# comparator_mezzanine.net
KiCad netlist of a schematic drawn in Altium Designer
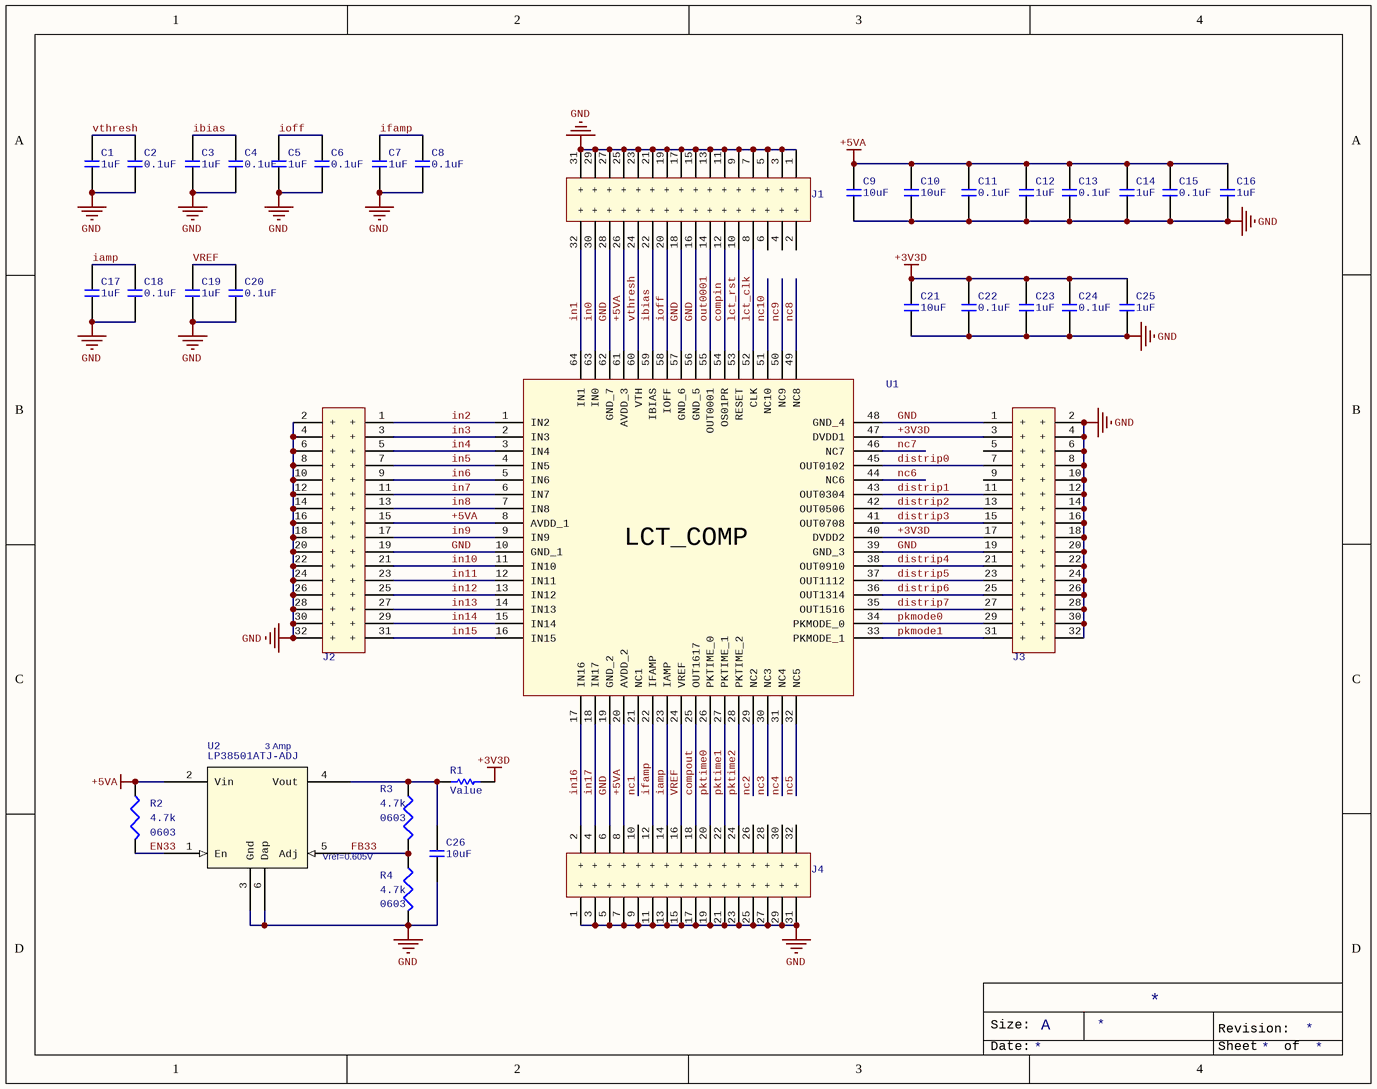
[diagram p0: comparator_mezzanine.SchDoc]

(export (version "E")
  (design (tool "Eeschema 10.0.6"))
  (components
    (comp (ref "C1")
      (value "1uF")
      (footprint "C0603")
      (description "CAP2, CER, 1.0uF, 10%, 25V, 0603")
      (libsource (lib "stdlib") (part "Murata/GRM188R61E105KA12D"))
    )
    (comp (ref "C2")
      (value "0.1uF")
      (footprint "C0603")
      (description "CAP-CER, 2, 0.1uF, 10%, 50V, 0603, X7R")
      (fields
        (field (name "MANUFACTURER") "AVX Corporation")
        (field (name "MANUFACTURER PART NUMBER") "06035C104KAT2A")
      )
      (libsource (lib "stdlib") (part "CAP/06035C104KAT2A"))
    )
    (comp (ref "C3")
      (value "1uF")
      (footprint "C0603")
      (description "CAP2, CER, 1.0uF, 10%, 25V, 0603")
      (libsource (lib "stdlib") (part "Murata/GRM188R61E105KA12D"))
    )
    (comp (ref "C4")
      (value "0.1uF")
      (footprint "C0603")
      (description "CAP-CER, 2, 0.1uF, 10%, 50V, 0603, X7R")
      (fields
        (field (name "MANUFACTURER") "AVX Corporation")
        (field (name "MANUFACTURER PART NUMBER") "06035C104KAT2A")
      )
      (libsource (lib "stdlib") (part "CAP/06035C104KAT2A"))
    )
    (comp (ref "C5")
      (value "1uF")
      (footprint "C0603")
      (description "CAP2, CER, 1.0uF, 10%, 25V, 0603")
      (libsource (lib "stdlib") (part "Murata/GRM188R61E105KA12D"))
    )
    (comp (ref "C6")
      (value "0.1uF")
      (footprint "C0603")
      (description "CAP-CER, 2, 0.1uF, 10%, 50V, 0603, X7R")
      (fields
        (field (name "MANUFACTURER") "AVX Corporation")
        (field (name "MANUFACTURER PART NUMBER") "06035C104KAT2A")
      )
      (libsource (lib "stdlib") (part "CAP/06035C104KAT2A"))
    )
    (comp (ref "C7")
      (value "1uF")
      (footprint "C0603")
      (description "CAP2, CER, 1.0uF, 10%, 25V, 0603")
      (libsource (lib "stdlib") (part "Murata/GRM188R61E105KA12D"))
    )
    (comp (ref "C8")
      (value "0.1uF")
      (footprint "C0603")
      (description "CAP-CER, 2, 0.1uF, 10%, 50V, 0603, X7R")
      (fields
        (field (name "MANUFACTURER") "AVX Corporation")
        (field (name "MANUFACTURER PART NUMBER") "06035C104KAT2A")
      )
      (libsource (lib "stdlib") (part "CAP/06035C104KAT2A"))
    )
    (comp (ref "C9")
      (value "10uF")
      (footprint "c1206")
      (description "CAP-CER, 2, 10uF, 10%, 35V, 1206")
      (fields
        (field (name "MANUFACTURER") "Taiyo Yuden")
        (field (name "MANUFACTURER PART NUMBER") "GMK316F106ZL-T")
      )
      (libsource (lib "stdlib") (part "CAP/GMK316F106ZL-T"))
    )
    (comp (ref "C10")
      (value "10uF")
      (footprint "c1206")
      (description "CAP-CER, 2, 10uF, 10%, 35V, 1206")
      (fields
        (field (name "MANUFACTURER") "Taiyo Yuden")
        (field (name "MANUFACTURER PART NUMBER") "GMK316F106ZL-T")
      )
      (libsource (lib "stdlib") (part "CAP/GMK316F106ZL-T"))
    )
    (comp (ref "C11")
      (value "0.1uF")
      (footprint "C0603")
      (description "CAP-CER, 2, 0.1uF, 10%, 50V, 0603, X7R")
      (fields
        (field (name "MANUFACTURER") "AVX Corporation")
        (field (name "MANUFACTURER PART NUMBER") "06035C104KAT2A")
      )
      (libsource (lib "stdlib") (part "CAP/06035C104KAT2A"))
    )
    (comp (ref "C12")
      (value "1uF")
      (footprint "C0603")
      (description "CAP2, CER, 1.0uF, 10%, 25V, 0603")
      (libsource (lib "stdlib") (part "Murata/GRM188R61E105KA12D"))
    )
    (comp (ref "C13")
      (value "0.1uF")
      (footprint "C0603")
      (description "CAP-CER, 2, 0.1uF, 10%, 50V, 0603, X7R")
      (fields
        (field (name "MANUFACTURER") "AVX Corporation")
        (field (name "MANUFACTURER PART NUMBER") "06035C104KAT2A")
      )
      (libsource (lib "stdlib") (part "CAP/06035C104KAT2A"))
    )
    (comp (ref "C14")
      (value "1uF")
      (footprint "C0603")
      (description "CAP2, CER, 1.0uF, 10%, 25V, 0603")
      (libsource (lib "stdlib") (part "Murata/GRM188R61E105KA12D"))
    )
    (comp (ref "C15")
      (value "0.1uF")
      (footprint "C0603")
      (description "CAP-CER, 2, 0.1uF, 10%, 50V, 0603, X7R")
      (fields
        (field (name "MANUFACTURER") "AVX Corporation")
        (field (name "MANUFACTURER PART NUMBER") "06035C104KAT2A")
      )
      (libsource (lib "stdlib") (part "CAP/06035C104KAT2A"))
    )
    (comp (ref "C16")
      (value "1uF")
      (footprint "C0603")
      (description "CAP2, CER, 1.0uF, 10%, 25V, 0603")
      (libsource (lib "stdlib") (part "Murata/GRM188R61E105KA12D"))
    )
    (comp (ref "C17")
      (value "1uF")
      (footprint "C0603")
      (description "CAP2, CER, 1.0uF, 10%, 25V, 0603")
      (libsource (lib "stdlib") (part "Murata/GRM188R61E105KA12D"))
    )
    (comp (ref "C18")
      (value "0.1uF")
      (footprint "C0603")
      (description "CAP-CER, 2, 0.1uF, 10%, 50V, 0603, X7R")
      (fields
        (field (name "MANUFACTURER") "AVX Corporation")
        (field (name "MANUFACTURER PART NUMBER") "06035C104KAT2A")
      )
      (libsource (lib "stdlib") (part "CAP/06035C104KAT2A"))
    )
    (comp (ref "C19")
      (value "1uF")
      (footprint "C0603")
      (description "CAP2, CER, 1.0uF, 10%, 25V, 0603")
      (libsource (lib "stdlib") (part "Murata/GRM188R61E105KA12D"))
    )
    (comp (ref "C20")
      (value "0.1uF")
      (footprint "C0603")
      (description "CAP-CER, 2, 0.1uF, 10%, 50V, 0603, X7R")
      (fields
        (field (name "MANUFACTURER") "AVX Corporation")
        (field (name "MANUFACTURER PART NUMBER") "06035C104KAT2A")
      )
      (libsource (lib "stdlib") (part "CAP/06035C104KAT2A"))
    )
    (comp (ref "C21")
      (value "10uF")
      (footprint "c1206")
      (description "CAP-CER, 2, 10uF, 10%, 35V, 1206")
      (fields
        (field (name "MANUFACTURER") "Taiyo Yuden")
        (field (name "MANUFACTURER PART NUMBER") "GMK316F106ZL-T")
      )
      (libsource (lib "stdlib") (part "CAP/GMK316F106ZL-T"))
    )
    (comp (ref "C22")
      (value "0.1uF")
      (footprint "C0603")
      (description "CAP-CER, 2, 0.1uF, 10%, 50V, 0603, X7R")
      (fields
        (field (name "MANUFACTURER") "AVX Corporation")
        (field (name "MANUFACTURER PART NUMBER") "06035C104KAT2A")
      )
      (libsource (lib "stdlib") (part "CAP/06035C104KAT2A"))
    )
    (comp (ref "C23")
      (value "1uF")
      (footprint "C0603")
      (description "CAP2, CER, 1.0uF, 10%, 25V, 0603")
      (libsource (lib "stdlib") (part "Murata/GRM188R61E105KA12D"))
    )
    (comp (ref "C24")
      (value "0.1uF")
      (footprint "C0603")
      (description "CAP-CER, 2, 0.1uF, 10%, 50V, 0603, X7R")
      (fields
        (field (name "MANUFACTURER") "AVX Corporation")
        (field (name "MANUFACTURER PART NUMBER") "06035C104KAT2A")
      )
      (libsource (lib "stdlib") (part "CAP/06035C104KAT2A"))
    )
    (comp (ref "C25")
      (value "1uF")
      (footprint "C0603")
      (description "CAP2, CER, 1.0uF, 10%, 25V, 0603")
      (libsource (lib "stdlib") (part "Murata/GRM188R61E105KA12D"))
    )
    (comp (ref "C26")
      (value "10uF")
      (footprint "c1206")
      (description "CAP-CER, 2, 10uF, 10%, 35V, 1206")
      (fields
        (field (name "MANUFACTURER") "Taiyo Yuden")
        (field (name "MANUFACTURER PART NUMBER") "GMK316F106ZL-T")
      )
      (libsource (lib "stdlib") (part "CAP/GMK316F106ZL-T"))
    )
    (comp (ref "J1")
      (value "HEADER 16x02")
      (footprint "HEADER 16X02")
      (libsource (lib "") (part "HEADER 16x02_1"))
    )
    (comp (ref "J2")
      (value "HEADER 16x02")
      (footprint "HEADER 16X02")
      (libsource (lib "") (part "HEADER 16x02_1"))
    )
    (comp (ref "J3")
      (value "HEADER 16x02")
      (footprint "HEADER 16X02")
      (libsource (lib "") (part "HEADER 16x02_2"))
    )
    (comp (ref "J4")
      (value "HEADER 16x02")
      (footprint "HEADER 16X02")
      (libsource (lib "stdlib") (part "HEADER 16x02"))
    )
    (comp (ref "R1")
      (value "Value")
      (footprint "R1206")
      (description "RES0, SMD 1206")
      (libsource (lib "stdlib") (part "RES SMD Generic 1206"))
    )
    (comp (ref "R2")
      (value "4.7k")
      (footprint "MC_S6/SM/R_0603_IPC")
      (description "RES SMD 4.7K OHM 1% 1/10W 0603")
      (fields
        (field (name "TOLERANCE") "±1%")
        (field (name "MANUFACTURER") "Panasonic Electronic Components")
        (field (name "SUPPLIER DEVICE PACKAGE") "0603")
      )
      (libsource (lib "ALCT_MEZ_SPARTAN6_Library") (part "ERJ-3EKF4701V"))
    )
    (comp (ref "R3")
      (value "4.7k")
      (footprint "MC_S6/SM/R_0603_IPC")
      (description "RES SMD 4.7K OHM 1% 1/10W 0603")
      (fields
        (field (name "TOLERANCE") "±1%")
        (field (name "MANUFACTURER") "Panasonic Electronic Components")
        (field (name "SUPPLIER DEVICE PACKAGE") "0603")
      )
      (libsource (lib "ALCT_MEZ_SPARTAN6_Library") (part "ERJ-3EKF4701V"))
    )
    (comp (ref "R4")
      (value "4.7k")
      (footprint "MC_S6/SM/R_0603_IPC")
      (description "RES SMD 4.7K OHM 1% 1/10W 0603")
      (fields
        (field (name "TOLERANCE") "±1%")
        (field (name "MANUFACTURER") "Panasonic Electronic Components")
        (field (name "SUPPLIER DEVICE PACKAGE") "0603")
      )
      (libsource (lib "ALCT_MEZ_SPARTAN6_Library") (part "ERJ-3EKF4701V"))
    )
    (comp (ref "U1")
      (value "UCLA/LCT_COMP")
      (footprint "TQFP-64 14x14mm")
      (description "UCLA LCT Comparator")
      (libsource (lib "stdlib") (part "UCLA/LCT_COMP"))
    )
    (comp (ref "U2")
      (value "LP38501ATJ-ADJ")
      (footprint "MC_S6/SM/TO263_THIN")
      (libsource (lib "ALCT_MEZ_SPARTAN6_Library") (part "LP38501ATJ-ADJ"))
    )
  )
  (nets
    (net (code "1") (name "+3V3D") (class "Default")
      (node (ref "C21") (pin "1") (pinfunction "5_1") (pintype "passive"))
      (node (ref "C22") (pin "2") (pinfunction "2_2") (pintype "passive"))
      (node (ref "C23") (pin "2") (pinfunction "2_2") (pintype "passive"))
      (node (ref "C24") (pin "2") (pinfunction "2_2") (pintype "passive"))
      (node (ref "C25") (pin "2") (pinfunction "2_2") (pintype "passive"))
      (node (ref "J3") (pin "17") (pinfunction "+_17") (pintype "passive"))
      (node (ref "J3") (pin "3") (pinfunction "+_3") (pintype "passive"))
      (node (ref "R1") (pin "2") (pinfunction "2_2") (pintype "passive"))
      (node (ref "U1") (pin "40") (pinfunction "DVDD2_40") (pintype "passive"))
      (node (ref "U1") (pin "47") (pinfunction "DVDD1_47") (pintype "passive"))
    )
    (net (code "2") (name "+5VA") (class "Default")
      (node (ref "C10") (pin "1") (pinfunction "5_1") (pintype "passive"))
      (node (ref "C11") (pin "2") (pinfunction "2_2") (pintype "passive"))
      (node (ref "C12") (pin "2") (pinfunction "2_2") (pintype "passive"))
      (node (ref "C13") (pin "2") (pinfunction "2_2") (pintype "passive"))
      (node (ref "C14") (pin "2") (pinfunction "2_2") (pintype "passive"))
      (node (ref "C15") (pin "2") (pinfunction "2_2") (pintype "passive"))
      (node (ref "C16") (pin "2") (pinfunction "2_2") (pintype "passive"))
      (node (ref "C9") (pin "1") (pinfunction "5_1") (pintype "passive"))
      (node (ref "J1") (pin "26") (pinfunction "+_26") (pintype "passive"))
      (node (ref "J2") (pin "15") (pinfunction "+_15") (pintype "passive"))
      (node (ref "J4") (pin "8") (pinfunction "+_8") (pintype "passive"))
      (node (ref "R2") (pin "1") (pinfunction "1_1") (pintype "passive"))
      (node (ref "U1") (pin "20") (pinfunction "AVDD_2_20") (pintype "passive"))
      (node (ref "U1") (pin "61") (pinfunction "AVDD_3_61") (pintype "passive"))
      (node (ref "U1") (pin "8") (pinfunction "AVDD_1_8") (pintype "passive"))
      (node (ref "U2") (pin "2") (pinfunction "Vin_2") (pintype "power_in"))
    )
    (net (code "3") (name "/EN33") (class "Default")
      (node (ref "R2") (pin "2") (pinfunction "2_2") (pintype "passive"))
      (node (ref "U2") (pin "1") (pinfunction "En_1") (pintype "input"))
    )
    (net (code "4") (name "/FB33") (class "Default")
      (node (ref "R3") (pin "2") (pinfunction "2_2") (pintype "passive"))
      (node (ref "R4") (pin "1") (pinfunction "1_1") (pintype "passive"))
      (node (ref "U2") (pin "5") (pinfunction "Adj_5") (pintype "input"))
    )
    (net (code "5") (name "/VREF") (class "Default")
      (node (ref "C19") (pin "2") (pinfunction "2_2") (pintype "passive"))
      (node (ref "C20") (pin "2") (pinfunction "2_2") (pintype "passive"))
      (node (ref "J4") (pin "16") (pinfunction "+_16") (pintype "passive"))
      (node (ref "U1") (pin "24") (pinfunction "VREF_24") (pintype "passive"))
    )
    (net (code "6") (name "/compin") (class "Default")
      (node (ref "J1") (pin "12") (pinfunction "+_12") (pintype "passive"))
      (node (ref "U1") (pin "54") (pinfunction "OS01PR_54") (pintype "passive"))
    )
    (net (code "7") (name "/compout") (class "Default")
      (node (ref "J4") (pin "18") (pinfunction "+_18") (pintype "passive"))
      (node (ref "U1") (pin "25") (pinfunction "OUT1617_25") (pintype "passive"))
    )
    (net (code "8") (name "/distrip0") (class "Default")
      (node (ref "J3") (pin "7") (pinfunction "+_7") (pintype "passive"))
      (node (ref "U1") (pin "45") (pinfunction "OUT0102_45") (pintype "passive"))
    )
    (net (code "9") (name "/distrip1") (class "Default")
      (node (ref "J3") (pin "11") (pinfunction "+_11") (pintype "passive"))
      (node (ref "U1") (pin "43") (pinfunction "OUT0304_43") (pintype "passive"))
    )
    (net (code "10") (name "/distrip2") (class "Default")
      (node (ref "J3") (pin "13") (pinfunction "+_13") (pintype "passive"))
      (node (ref "U1") (pin "42") (pinfunction "OUT0506_42") (pintype "passive"))
    )
    (net (code "11") (name "/distrip3") (class "Default")
      (node (ref "J3") (pin "15") (pinfunction "+_15") (pintype "passive"))
      (node (ref "U1") (pin "41") (pinfunction "OUT0708_41") (pintype "passive"))
    )
    (net (code "12") (name "/distrip4") (class "Default")
      (node (ref "J3") (pin "21") (pinfunction "+_21") (pintype "passive"))
      (node (ref "U1") (pin "38") (pinfunction "OUT0910_38") (pintype "passive"))
    )
    (net (code "13") (name "/distrip5") (class "Default")
      (node (ref "J3") (pin "23") (pinfunction "+_23") (pintype "passive"))
      (node (ref "U1") (pin "37") (pinfunction "OUT1112_37") (pintype "passive"))
    )
    (net (code "14") (name "/distrip6") (class "Default")
      (node (ref "J3") (pin "25") (pinfunction "+_25") (pintype "passive"))
      (node (ref "U1") (pin "36") (pinfunction "OUT1314_36") (pintype "passive"))
    )
    (net (code "15") (name "/distrip7") (class "Default")
      (node (ref "J3") (pin "27") (pinfunction "+_27") (pintype "passive"))
      (node (ref "U1") (pin "35") (pinfunction "OUT1516_35") (pintype "passive"))
    )
    (net (code "16") (name "/iamp") (class "Default")
      (node (ref "C17") (pin "2") (pinfunction "2_2") (pintype "passive"))
      (node (ref "C18") (pin "2") (pinfunction "2_2") (pintype "passive"))
      (node (ref "J4") (pin "14") (pinfunction "+_14") (pintype "passive"))
      (node (ref "U1") (pin "23") (pinfunction "IAMP_23") (pintype "passive"))
    )
    (net (code "17") (name "/ibias") (class "Default")
      (node (ref "C3") (pin "2") (pinfunction "2_2") (pintype "passive"))
      (node (ref "C4") (pin "2") (pinfunction "2_2") (pintype "passive"))
      (node (ref "J1") (pin "22") (pinfunction "+_22") (pintype "passive"))
      (node (ref "U1") (pin "59") (pinfunction "IBIAS_59") (pintype "passive"))
    )
    (net (code "18") (name "/ifamp") (class "Default")
      (node (ref "C7") (pin "2") (pinfunction "2_2") (pintype "passive"))
      (node (ref "C8") (pin "2") (pinfunction "2_2") (pintype "passive"))
      (node (ref "J4") (pin "12") (pinfunction "+_12") (pintype "passive"))
      (node (ref "U1") (pin "22") (pinfunction "IFAMP_22") (pintype "passive"))
    )
    (net (code "19") (name "/in0") (class "Default")
      (node (ref "J1") (pin "30") (pinfunction "+_30") (pintype "passive"))
      (node (ref "U1") (pin "63") (pinfunction "IN0_63") (pintype "passive"))
    )
    (net (code "20") (name "/in1") (class "Default")
      (node (ref "J1") (pin "32") (pinfunction "+_32") (pintype "passive"))
      (node (ref "U1") (pin "64") (pinfunction "IN1_64") (pintype "passive"))
    )
    (net (code "21") (name "/in2") (class "Default")
      (node (ref "J2") (pin "1") (pinfunction "+_1") (pintype "passive"))
      (node (ref "U1") (pin "1") (pinfunction "IN2_1") (pintype "passive"))
    )
    (net (code "22") (name "/in3") (class "Default")
      (node (ref "J2") (pin "3") (pinfunction "+_3") (pintype "passive"))
      (node (ref "U1") (pin "2") (pinfunction "IN3_2") (pintype "passive"))
    )
    (net (code "23") (name "/in4") (class "Default")
      (node (ref "J2") (pin "5") (pinfunction "+_5") (pintype "passive"))
      (node (ref "U1") (pin "3") (pinfunction "IN4_3") (pintype "passive"))
    )
    (net (code "24") (name "/in5") (class "Default")
      (node (ref "J2") (pin "7") (pinfunction "+_7") (pintype "passive"))
      (node (ref "U1") (pin "4") (pinfunction "IN5_4") (pintype "passive"))
    )
    (net (code "25") (name "/in6") (class "Default")
      (node (ref "J2") (pin "9") (pinfunction "+_9") (pintype "passive"))
      (node (ref "U1") (pin "5") (pinfunction "IN6_5") (pintype "passive"))
    )
    (net (code "26") (name "/in7") (class "Default")
      (node (ref "J2") (pin "11") (pinfunction "+_11") (pintype "passive"))
      (node (ref "U1") (pin "6") (pinfunction "IN7_6") (pintype "passive"))
    )
    (net (code "27") (name "/in8") (class "Default")
      (node (ref "J2") (pin "13") (pinfunction "+_13") (pintype "passive"))
      (node (ref "U1") (pin "7") (pinfunction "IN8_7") (pintype "passive"))
    )
    (net (code "28") (name "/in9") (class "Default")
      (node (ref "J2") (pin "17") (pinfunction "+_17") (pintype "passive"))
      (node (ref "U1") (pin "9") (pinfunction "IN9_9") (pintype "passive"))
    )
    (net (code "29") (name "/in10") (class "Default")
      (node (ref "J2") (pin "21") (pinfunction "+_21") (pintype "passive"))
      (node (ref "U1") (pin "11") (pinfunction "IN10_11") (pintype "passive"))
    )
    (net (code "30") (name "/in11") (class "Default")
      (node (ref "J2") (pin "23") (pinfunction "+_23") (pintype "passive"))
      (node (ref "U1") (pin "12") (pinfunction "IN11_12") (pintype "passive"))
    )
    (net (code "31") (name "/in12") (class "Default")
      (node (ref "J2") (pin "25") (pinfunction "+_25") (pintype "passive"))
      (node (ref "U1") (pin "13") (pinfunction "IN12_13") (pintype "passive"))
    )
    (net (code "32") (name "/in13") (class "Default")
      (node (ref "J2") (pin "27") (pinfunction "+_27") (pintype "passive"))
      (node (ref "U1") (pin "14") (pinfunction "IN13_14") (pintype "passive"))
    )
    (net (code "33") (name "/in14") (class "Default")
      (node (ref "J2") (pin "29") (pinfunction "+_29") (pintype "passive"))
      (node (ref "U1") (pin "15") (pinfunction "IN14_15") (pintype "passive"))
    )
    (net (code "34") (name "/in15") (class "Default")
      (node (ref "J2") (pin "31") (pinfunction "+_31") (pintype "passive"))
      (node (ref "U1") (pin "16") (pinfunction "IN15_16") (pintype "passive"))
    )
    (net (code "35") (name "/in16") (class "Default")
      (node (ref "J4") (pin "2") (pinfunction "+_2") (pintype "passive"))
      (node (ref "U1") (pin "17") (pinfunction "IN16_17") (pintype "passive"))
    )
    (net (code "36") (name "/in17") (class "Default")
      (node (ref "J4") (pin "4") (pinfunction "+_4") (pintype "passive"))
      (node (ref "U1") (pin "18") (pinfunction "IN17_18") (pintype "passive"))
    )
    (net (code "37") (name "/ioff") (class "Default")
      (node (ref "C5") (pin "2") (pinfunction "2_2") (pintype "passive"))
      (node (ref "C6") (pin "2") (pinfunction "2_2") (pintype "passive"))
      (node (ref "J1") (pin "20") (pinfunction "+_20") (pintype "passive"))
      (node (ref "U1") (pin "58") (pinfunction "IOFF_58") (pintype "passive"))
    )
    (net (code "38") (name "/lct_clk") (class "Default")
      (node (ref "J1") (pin "8") (pinfunction "+_8") (pintype "passive"))
      (node (ref "U1") (pin "52") (pinfunction "CLK_52") (pintype "passive"))
    )
    (net (code "39") (name "/lct_rst") (class "Default")
      (node (ref "J1") (pin "10") (pinfunction "+_10") (pintype "passive"))
      (node (ref "U1") (pin "53") (pinfunction "RESET_53") (pintype "passive"))
    )
    (net (code "40") (name "/nc1") (class "Default")
      (node (ref "U1") (pin "21") (pinfunction "NC1_21") (pintype "passive"))
    )
    (net (code "41") (name "/nc2") (class "Default")
      (node (ref "U1") (pin "29") (pinfunction "NC2_29") (pintype "passive"))
    )
    (net (code "42") (name "/nc3") (class "Default")
      (node (ref "U1") (pin "30") (pinfunction "NC3_30") (pintype "passive"))
    )
    (net (code "43") (name "/nc4") (class "Default")
      (node (ref "U1") (pin "31") (pinfunction "NC4_31") (pintype "passive"))
    )
    (net (code "44") (name "/nc5") (class "Default")
      (node (ref "U1") (pin "32") (pinfunction "NC5_32") (pintype "passive"))
    )
    (net (code "45") (name "/nc6") (class "Default")
      (node (ref "U1") (pin "44") (pinfunction "NC6_44") (pintype "passive"))
    )
    (net (code "46") (name "/nc7") (class "Default")
      (node (ref "U1") (pin "46") (pinfunction "NC7_46") (pintype "passive"))
    )
    (net (code "47") (name "/nc8") (class "Default")
      (node (ref "U1") (pin "49") (pinfunction "NC8_49") (pintype "passive"))
    )
    (net (code "48") (name "/nc9") (class "Default")
      (node (ref "U1") (pin "50") (pinfunction "NC9_50") (pintype "passive"))
    )
    (net (code "49") (name "/nc10") (class "Default")
      (node (ref "U1") (pin "51") (pinfunction "NC10_51") (pintype "passive"))
    )
    (net (code "50") (name "/out0001") (class "Default")
      (node (ref "J1") (pin "14") (pinfunction "+_14") (pintype "passive"))
      (node (ref "U1") (pin "55") (pinfunction "OUT0001_55") (pintype "passive"))
    )
    (net (code "51") (name "/pkmode0") (class "Default")
      (node (ref "J3") (pin "29") (pinfunction "+_29") (pintype "passive"))
      (node (ref "U1") (pin "34") (pinfunction "PKMODE_0_34") (pintype "passive"))
    )
    (net (code "52") (name "/pkmode1") (class "Default")
      (node (ref "J3") (pin "31") (pinfunction "+_31") (pintype "passive"))
      (node (ref "U1") (pin "33") (pinfunction "PKMODE_1_33") (pintype "passive"))
    )
    (net (code "53") (name "/pktime0") (class "Default")
      (node (ref "J4") (pin "20") (pinfunction "+_20") (pintype "passive"))
      (node (ref "U1") (pin "26") (pinfunction "PKTIME_0_26") (pintype "passive"))
    )
    (net (code "54") (name "/pktime1") (class "Default")
      (node (ref "J4") (pin "22") (pinfunction "+_22") (pintype "passive"))
      (node (ref "U1") (pin "27") (pinfunction "PKTIME_1_27") (pintype "passive"))
    )
    (net (code "55") (name "/pktime2") (class "Default")
      (node (ref "J4") (pin "24") (pinfunction "+_24") (pintype "passive"))
      (node (ref "U1") (pin "28") (pinfunction "PKTIME_2_28") (pintype "passive"))
    )
    (net (code "56") (name "/vthresh") (class "Default")
      (node (ref "C1") (pin "2") (pinfunction "2_2") (pintype "passive"))
      (node (ref "C2") (pin "2") (pinfunction "2_2") (pintype "passive"))
      (node (ref "J1") (pin "24") (pinfunction "+_24") (pintype "passive"))
      (node (ref "U1") (pin "60") (pinfunction "VTH_60") (pintype "passive"))
    )
    (net (code "57") (name "GND") (class "Default")
      (node (ref "C1") (pin "1") (pinfunction "5_1") (pintype "passive"))
      (node (ref "C10") (pin "2") (pinfunction "2_2") (pintype "passive"))
      (node (ref "C11") (pin "1") (pinfunction "5_1") (pintype "passive"))
      (node (ref "C12") (pin "1") (pinfunction "5_1") (pintype "passive"))
      (node (ref "C13") (pin "1") (pinfunction "5_1") (pintype "passive"))
      (node (ref "C14") (pin "1") (pinfunction "5_1") (pintype "passive"))
      (node (ref "C15") (pin "1") (pinfunction "5_1") (pintype "passive"))
      (node (ref "C16") (pin "1") (pinfunction "5_1") (pintype "passive"))
      (node (ref "C17") (pin "1") (pinfunction "5_1") (pintype "passive"))
      (node (ref "C18") (pin "1") (pinfunction "5_1") (pintype "passive"))
      (node (ref "C19") (pin "1") (pinfunction "5_1") (pintype "passive"))
      (node (ref "C2") (pin "1") (pinfunction "5_1") (pintype "passive"))
      (node (ref "C20") (pin "1") (pinfunction "5_1") (pintype "passive"))
      (node (ref "C21") (pin "2") (pinfunction "2_2") (pintype "passive"))
      (node (ref "C22") (pin "1") (pinfunction "5_1") (pintype "passive"))
      (node (ref "C23") (pin "1") (pinfunction "5_1") (pintype "passive"))
      (node (ref "C24") (pin "1") (pinfunction "5_1") (pintype "passive"))
      (node (ref "C25") (pin "1") (pinfunction "5_1") (pintype "passive"))
      (node (ref "C26") (pin "2") (pinfunction "2_2") (pintype "passive"))
      (node (ref "C3") (pin "1") (pinfunction "5_1") (pintype "passive"))
      (node (ref "C4") (pin "1") (pinfunction "5_1") (pintype "passive"))
      (node (ref "C5") (pin "1") (pinfunction "5_1") (pintype "passive"))
      (node (ref "C6") (pin "1") (pinfunction "5_1") (pintype "passive"))
      (node (ref "C7") (pin "1") (pinfunction "5_1") (pintype "passive"))
      (node (ref "C8") (pin "1") (pinfunction "5_1") (pintype "passive"))
      (node (ref "C9") (pin "2") (pinfunction "2_2") (pintype "passive"))
      (node (ref "J1") (pin "1") (pinfunction "+_1") (pintype "passive"))
      (node (ref "J1") (pin "11") (pinfunction "+_11") (pintype "passive"))
      (node (ref "J1") (pin "13") (pinfunction "+_13") (pintype "passive"))
      (node (ref "J1") (pin "15") (pinfunction "+_15") (pintype "passive"))
      (node (ref "J1") (pin "16") (pinfunction "+_16") (pintype "passive"))
      (node (ref "J1") (pin "17") (pinfunction "+_17") (pintype "passive"))
      (node (ref "J1") (pin "18") (pinfunction "+_18") (pintype "passive"))
      (node (ref "J1") (pin "19") (pinfunction "+_19") (pintype "passive"))
      (node (ref "J1") (pin "21") (pinfunction "+_21") (pintype "passive"))
      (node (ref "J1") (pin "23") (pinfunction "+_23") (pintype "passive"))
      (node (ref "J1") (pin "25") (pinfunction "+_25") (pintype "passive"))
      (node (ref "J1") (pin "27") (pinfunction "+_27") (pintype "passive"))
      (node (ref "J1") (pin "28") (pinfunction "+_28") (pintype "passive"))
      (node (ref "J1") (pin "29") (pinfunction "+_29") (pintype "passive"))
      (node (ref "J1") (pin "3") (pinfunction "+_3") (pintype "passive"))
      (node (ref "J1") (pin "31") (pinfunction "+_31") (pintype "passive"))
      (node (ref "J1") (pin "5") (pinfunction "+_5") (pintype "passive"))
      (node (ref "J1") (pin "7") (pinfunction "+_7") (pintype "passive"))
      (node (ref "J1") (pin "9") (pinfunction "+_9") (pintype "passive"))
      (node (ref "J2") (pin "10") (pinfunction "+_10") (pintype "passive"))
      (node (ref "J2") (pin "12") (pinfunction "+_12") (pintype "passive"))
      (node (ref "J2") (pin "14") (pinfunction "+_14") (pintype "passive"))
      (node (ref "J2") (pin "16") (pinfunction "+_16") (pintype "passive"))
      (node (ref "J2") (pin "18") (pinfunction "+_18") (pintype "passive"))
      (node (ref "J2") (pin "19") (pinfunction "+_19") (pintype "passive"))
      (node (ref "J2") (pin "2") (pinfunction "+_2") (pintype "passive"))
      (node (ref "J2") (pin "20") (pinfunction "+_20") (pintype "passive"))
      (node (ref "J2") (pin "22") (pinfunction "+_22") (pintype "passive"))
      (node (ref "J2") (pin "24") (pinfunction "+_24") (pintype "passive"))
      (node (ref "J2") (pin "26") (pinfunction "+_26") (pintype "passive"))
      (node (ref "J2") (pin "28") (pinfunction "+_28") (pintype "passive"))
      (node (ref "J2") (pin "30") (pinfunction "+_30") (pintype "passive"))
      (node (ref "J2") (pin "32") (pinfunction "+_32") (pintype "passive"))
      (node (ref "J2") (pin "4") (pinfunction "+_4") (pintype "passive"))
      (node (ref "J2") (pin "6") (pinfunction "+_6") (pintype "passive"))
      (node (ref "J2") (pin "8") (pinfunction "+_8") (pintype "passive"))
      (node (ref "J3") (pin "1") (pinfunction "+_1") (pintype "passive"))
      (node (ref "J3") (pin "10") (pinfunction "+_10") (pintype "passive"))
      (node (ref "J3") (pin "12") (pinfunction "+_12") (pintype "passive"))
      (node (ref "J3") (pin "14") (pinfunction "+_14") (pintype "passive"))
      (node (ref "J3") (pin "16") (pinfunction "+_16") (pintype "passive"))
      (node (ref "J3") (pin "18") (pinfunction "+_18") (pintype "passive"))
      (node (ref "J3") (pin "19") (pinfunction "+_19") (pintype "passive"))
      (node (ref "J3") (pin "2") (pinfunction "+_2") (pintype "passive"))
      (node (ref "J3") (pin "20") (pinfunction "+_20") (pintype "passive"))
      (node (ref "J3") (pin "22") (pinfunction "+_22") (pintype "passive"))
      (node (ref "J3") (pin "24") (pinfunction "+_24") (pintype "passive"))
      (node (ref "J3") (pin "26") (pinfunction "+_26") (pintype "passive"))
      (node (ref "J3") (pin "28") (pinfunction "+_28") (pintype "passive"))
      (node (ref "J3") (pin "30") (pinfunction "+_30") (pintype "passive"))
      (node (ref "J3") (pin "32") (pinfunction "+_32") (pintype "passive"))
      (node (ref "J3") (pin "4") (pinfunction "+_4") (pintype "passive"))
      (node (ref "J3") (pin "6") (pinfunction "+_6") (pintype "passive"))
      (node (ref "J3") (pin "8") (pinfunction "+_8") (pintype "passive"))
      (node (ref "J4") (pin "1") (pinfunction "+_1") (pintype "passive"))
      (node (ref "J4") (pin "11") (pinfunction "+_11") (pintype "passive"))
      (node (ref "J4") (pin "13") (pinfunction "+_13") (pintype "passive"))
      (node (ref "J4") (pin "15") (pinfunction "+_15") (pintype "passive"))
      (node (ref "J4") (pin "17") (pinfunction "+_17") (pintype "passive"))
      (node (ref "J4") (pin "19") (pinfunction "+_19") (pintype "passive"))
      (node (ref "J4") (pin "21") (pinfunction "+_21") (pintype "passive"))
      (node (ref "J4") (pin "23") (pinfunction "+_23") (pintype "passive"))
      (node (ref "J4") (pin "25") (pinfunction "+_25") (pintype "passive"))
      (node (ref "J4") (pin "27") (pinfunction "+_27") (pintype "passive"))
      (node (ref "J4") (pin "29") (pinfunction "+_29") (pintype "passive"))
      (node (ref "J4") (pin "3") (pinfunction "+_3") (pintype "passive"))
      (node (ref "J4") (pin "31") (pinfunction "+_31") (pintype "passive"))
      (node (ref "J4") (pin "5") (pinfunction "+_5") (pintype "passive"))
      (node (ref "J4") (pin "6") (pinfunction "+_6") (pintype "passive"))
      (node (ref "J4") (pin "7") (pinfunction "+_7") (pintype "passive"))
      (node (ref "J4") (pin "9") (pinfunction "+_9") (pintype "passive"))
      (node (ref "R4") (pin "2") (pinfunction "2_2") (pintype "passive"))
      (node (ref "U1") (pin "10") (pinfunction "GND_1_10") (pintype "passive"))
      (node (ref "U1") (pin "19") (pinfunction "GND_2_19") (pintype "passive"))
      (node (ref "U1") (pin "39") (pinfunction "GND_3_39") (pintype "passive"))
      (node (ref "U1") (pin "48") (pinfunction "GND_4_48") (pintype "passive"))
      (node (ref "U1") (pin "56") (pinfunction "GND_5_56") (pintype "passive"))
      (node (ref "U1") (pin "57") (pinfunction "GND_6_57") (pintype "passive"))
      (node (ref "U1") (pin "62") (pinfunction "GND_7_62") (pintype "passive"))
      (node (ref "U2") (pin "3") (pinfunction "Gnd_3") (pintype "power_in"))
      (node (ref "U2") (pin "6") (pinfunction "Dap_6") (pintype "power_in"))
    )
    (net (code "58") (name "Net-(C26-5)") (class "Default")
      (node (ref "C26") (pin "1") (pinfunction "5_1") (pintype "passive"))
      (node (ref "R1") (pin "1") (pinfunction "1_1") (pintype "passive"))
      (node (ref "R3") (pin "1") (pinfunction "1_1") (pintype "passive"))
      (node (ref "U2") (pin "4") (pinfunction "Vout_4") (pintype "power_in"))
    )
    (net (code "59") (name "unconnected-(J1-+-Pad2)") (class "Default")
      (node (ref "J1") (pin "2") (pinfunction "+_2") (pintype "passive"))
    )
    (net (code "60") (name "unconnected-(J1-+-Pad4)") (class "Default")
      (node (ref "J1") (pin "4") (pinfunction "+_4") (pintype "passive"))
    )
    (net (code "61") (name "unconnected-(J1-+-Pad6)") (class "Default")
      (node (ref "J1") (pin "6") (pinfunction "+_6") (pintype "passive"))
    )
    (net (code "62") (name "unconnected-(J3-+-Pad5)") (class "Default")
      (node (ref "J3") (pin "5") (pinfunction "+_5") (pintype "passive"))
    )
    (net (code "63") (name "unconnected-(J3-+-Pad9)") (class "Default")
      (node (ref "J3") (pin "9") (pinfunction "+_9") (pintype "passive"))
    )
    (net (code "64") (name "unconnected-(J4-+-Pad10)") (class "Default")
      (node (ref "J4") (pin "10") (pinfunction "+_10") (pintype "passive"))
    )
    (net (code "65") (name "unconnected-(J4-+-Pad26)") (class "Default")
      (node (ref "J4") (pin "26") (pinfunction "+_26") (pintype "passive"))
    )
    (net (code "66") (name "unconnected-(J4-+-Pad28)") (class "Default")
      (node (ref "J4") (pin "28") (pinfunction "+_28") (pintype "passive"))
    )
    (net (code "67") (name "unconnected-(J4-+-Pad30)") (class "Default")
      (node (ref "J4") (pin "30") (pinfunction "+_30") (pintype "passive"))
    )
    (net (code "68") (name "unconnected-(J4-+-Pad32)") (class "Default")
      (node (ref "J4") (pin "32") (pinfunction "+_32") (pintype "passive"))
    )
  )
)
